# CAN_ProtoBoard_Pro_Mini.net
KiCad netlist of a schematic drawn in EAGLE
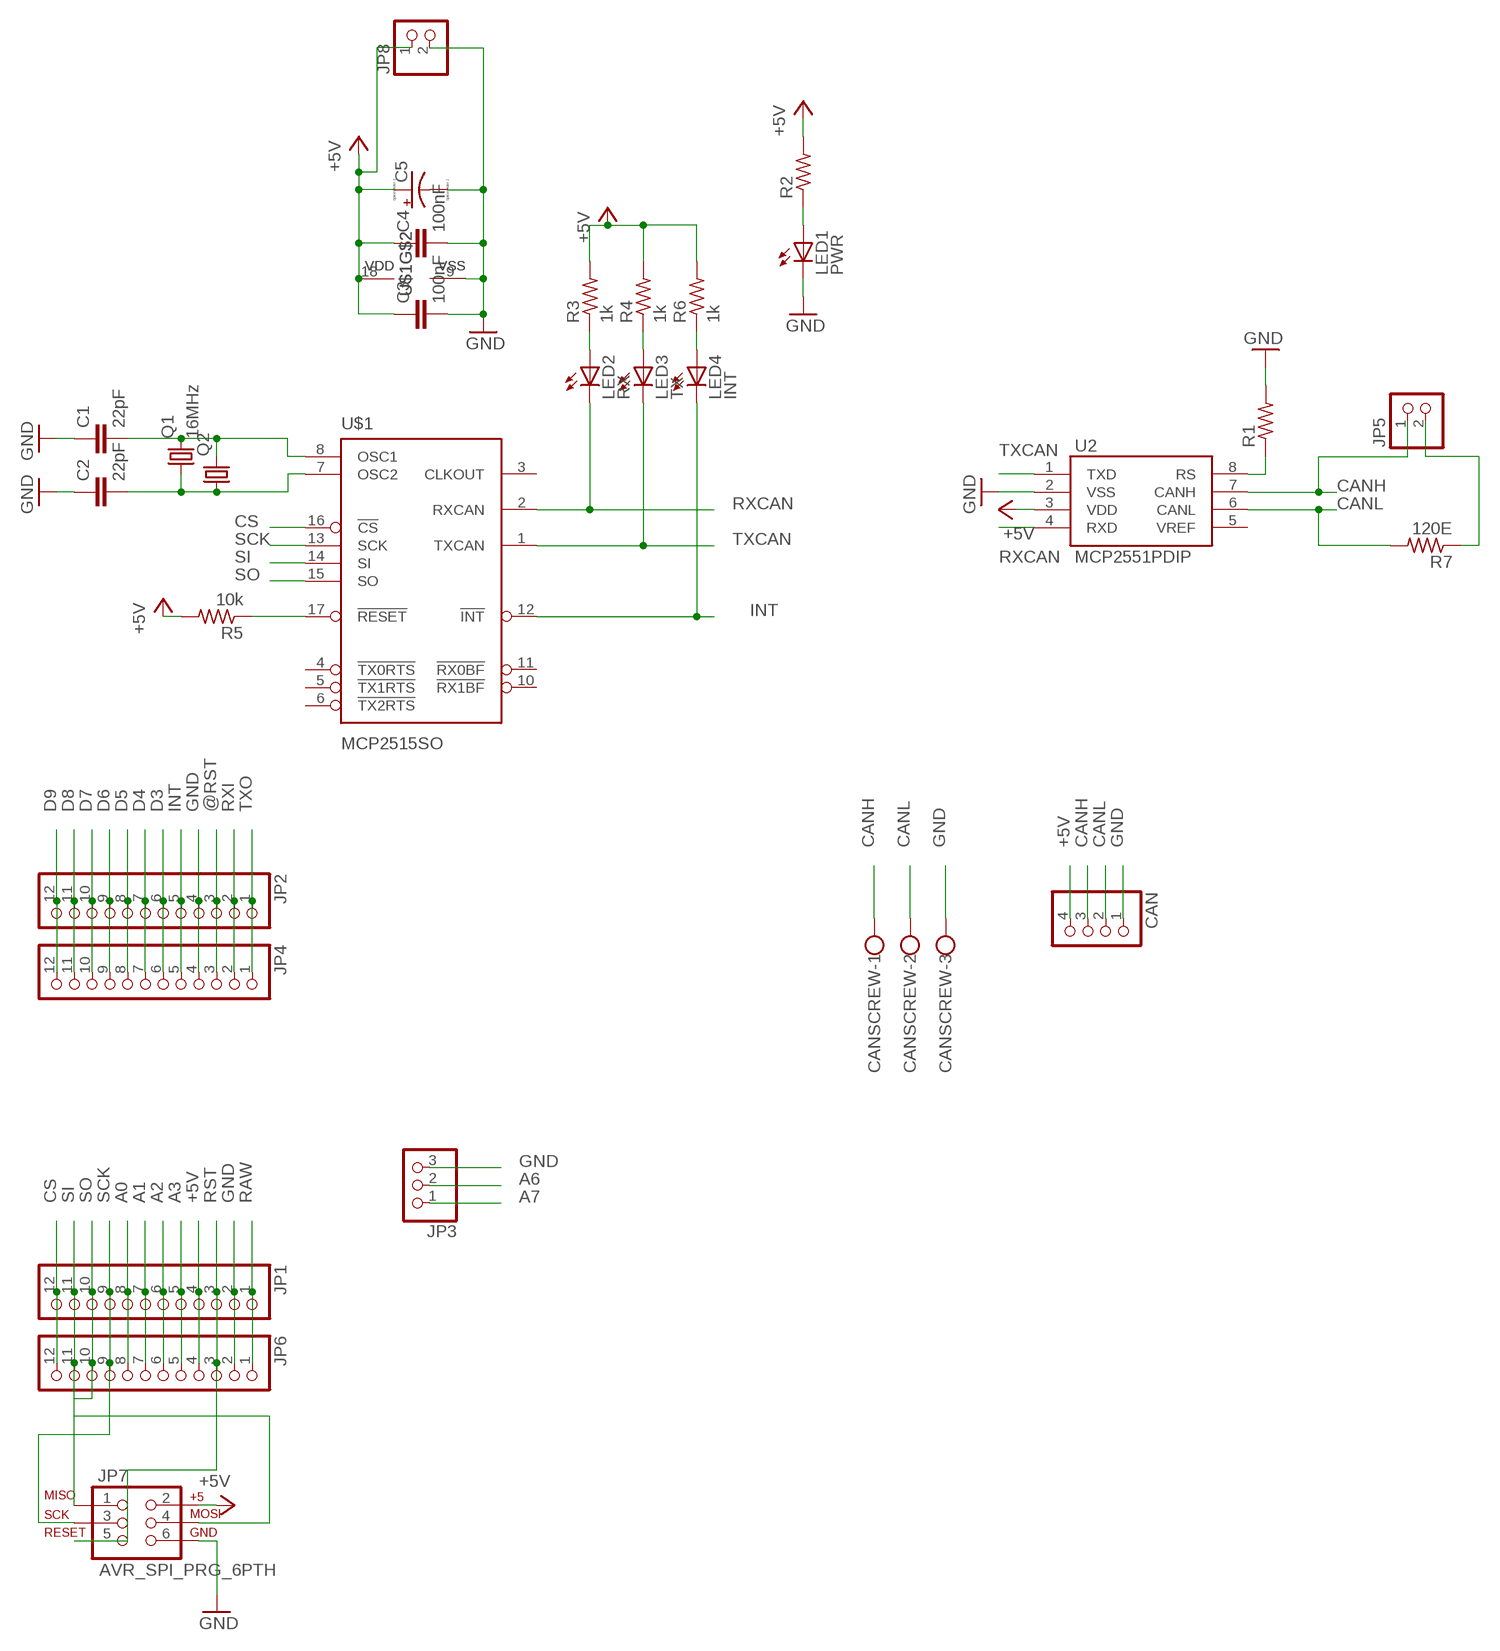
[diagram p0: schematic, sheet 1]

(export (version "E")
  (design (tool "Eeschema 10.0.6"))
  (components
    (comp (ref "C1")
      (value "22pF")
      (footprint "eagle-import:C0805K")
      (libsource (lib "eagle-import") (part "C-EUC0805K"))
    )
    (comp (ref "C2")
      (value "22pF")
      (footprint "eagle-import:C0805K")
      (libsource (lib "eagle-import") (part "C-EUC0805K"))
    )
    (comp (ref "C3")
      (value "100nF")
      (footprint "eagle-import:C0805K")
      (libsource (lib "eagle-import") (part "C-EUC0805K"))
    )
    (comp (ref "C4")
      (value "100nF")
      (footprint "eagle-import:C0805K")
      (libsource (lib "eagle-import") (part "C-EUC0805K"))
    )
    (comp (ref "C5")
      (value "CPOL-USE5-8.5")
      (footprint "eagle-import:E5-8,5")
      (libsource (lib "eagle-import") (part "CPOL-USE5-8.5"))
    )
    (comp (ref "CAN")
      (value "PINHD-1X4")
      (footprint "eagle-import:1X04")
      (libsource (lib "eagle-import") (part "PINHD-1X4"))
    )
    (comp (ref "CANSCREW")
      (value "W237-103")
      (footprint "eagle-import:W237-103")
      (fields (field (name "MPN") "237-103"))
      (libsource (lib "eagle-import") (part "W237-103"))
    )
    (comp (ref "JP1")
      (value "PINHD-1X12")
      (footprint "eagle-import:1X12")
      (libsource (lib "eagle-import") (part "PINHD-1X12"))
    )
    (comp (ref "JP2")
      (value "PINHD-1X12")
      (footprint "eagle-import:1X12")
      (libsource (lib "eagle-import") (part "PINHD-1X12"))
    )
    (comp (ref "JP3")
      (value "PINHD-1X3")
      (footprint "eagle-import:1X03")
      (libsource (lib "eagle-import") (part "PINHD-1X3"))
    )
    (comp (ref "JP4")
      (value "PINHD-1X12")
      (footprint "eagle-import:1X12")
      (libsource (lib "eagle-import") (part "PINHD-1X12"))
    )
    (comp (ref "JP5")
      (value "PINHD-1X2")
      (footprint "eagle-import:1X02")
      (libsource (lib "eagle-import") (part "PINHD-1X2"))
    )
    (comp (ref "JP6")
      (value "PINHD-1X12")
      (footprint "eagle-import:1X12")
      (libsource (lib "eagle-import") (part "PINHD-1X12"))
    )
    (comp (ref "JP7")
      (value "AVR_SPI_PRG_6PTH")
      (footprint "eagle-import:2X3")
      (libsource (lib "eagle-import") (part "AVR_SPI_PRG_6PTH"))
    )
    (comp (ref "JP8")
      (value "PINHD-1X2")
      (footprint "eagle-import:1X02")
      (libsource (lib "eagle-import") (part "PINHD-1X2"))
    )
    (comp (ref "LED1")
      (value "PWR")
      (footprint "eagle-import:LED3MM")
      (libsource (lib "eagle-import") (part "LED3MM"))
    )
    (comp (ref "LED2")
      (value "RX")
      (footprint "eagle-import:LED3MM")
      (libsource (lib "eagle-import") (part "LED3MM"))
    )
    (comp (ref "LED3")
      (value "TX")
      (footprint "eagle-import:LED3MM")
      (libsource (lib "eagle-import") (part "LED3MM"))
    )
    (comp (ref "LED4")
      (value "INT")
      (footprint "eagle-import:LED3MM")
      (libsource (lib "eagle-import") (part "LED3MM"))
    )
    (comp (ref "Q1")
      (value "16MHz")
      (footprint "eagle-import:HC49_S")
      (libsource (lib "eagle-import") (part "CRYSTALHC49S"))
    )
    (comp (ref "Q2")
      (value "CRYSTALHC49UP")
      (footprint "eagle-import:HC49UP")
      (libsource (lib "eagle-import") (part "CRYSTALHC49UP"))
    )
    (comp (ref "R1")
      (value "R-US_R0805")
      (footprint "eagle-import:R0805")
      (libsource (lib "eagle-import") (part "R-US_R0805"))
    )
    (comp (ref "R2")
      (value "R-US_R0805")
      (footprint "eagle-import:R0805")
      (libsource (lib "eagle-import") (part "R-US_R0805"))
    )
    (comp (ref "R3")
      (value "1k")
      (footprint "eagle-import:R0805")
      (libsource (lib "eagle-import") (part "R-US_R0805"))
    )
    (comp (ref "R4")
      (value "1k")
      (footprint "eagle-import:R0805")
      (libsource (lib "eagle-import") (part "R-US_R0805"))
    )
    (comp (ref "R5")
      (value "10k")
      (footprint "eagle-import:R0805")
      (libsource (lib "eagle-import") (part "R-US_R0805"))
    )
    (comp (ref "R6")
      (value "1k")
      (footprint "eagle-import:R0805")
      (libsource (lib "eagle-import") (part "R-US_R0805"))
    )
    (comp (ref "R7")
      (value "120E")
      (footprint "eagle-import:R0805")
      (libsource (lib "eagle-import") (part "R-US_R0805"))
    )
    (comp (ref "U$1")
      (value "MCP2515SO")
      (footprint "eagle-import:SO-18W")
      (libsource (lib "eagle-import") (part "MCP2515SO"))
    )
    (comp (ref "U2")
      (value "MCP2551PDIP")
      (footprint "eagle-import:DIL08")
      (libsource (lib "eagle-import") (part "MCP2551PDIP"))
    )
  )
  (nets
    (net (code "1") (name "+5V") (class "Default")
      (node (ref "C3") (pin "1") (pinfunction "1_1") (pintype "passive"))
      (node (ref "C4") (pin "1") (pinfunction "1_1") (pintype "passive"))
      (node (ref "C5") (pin "+") (pinfunction "+_+") (pintype "passive"))
      (node (ref "CAN") (pin "4") (pinfunction "4_4") (pintype "passive"))
      (node (ref "JP1") (pin "4") (pinfunction "4_4") (pintype "passive"))
      (node (ref "JP6") (pin "4") (pinfunction "4_4") (pintype "passive"))
      (node (ref "JP7") (pin "2") (pinfunction "2_2") (pintype "passive"))
      (node (ref "JP8") (pin "1") (pinfunction "1_1") (pintype "passive"))
      (node (ref "R2") (pin "2") (pinfunction "2_2") (pintype "passive"))
      (node (ref "R3") (pin "2") (pinfunction "2_2") (pintype "passive"))
      (node (ref "R4") (pin "2") (pinfunction "2_2") (pintype "passive"))
      (node (ref "R5") (pin "2") (pinfunction "2_2") (pintype "passive"))
      (node (ref "R6") (pin "2") (pinfunction "2_2") (pintype "passive"))
      (node (ref "U$1") (pin "18") (pinfunction "VDD_18") (pintype "power_in"))
      (node (ref "U2") (pin "3") (pinfunction "VDD_3") (pintype "bidirectional"))
    )
    (net (code "2") (name "/@RST") (class "Default")
      (node (ref "JP2") (pin "3") (pinfunction "3_3") (pintype "passive"))
      (node (ref "JP4") (pin "3") (pinfunction "3_3") (pintype "passive"))
    )
    (net (code "3") (name "/A0") (class "Default")
      (node (ref "JP1") (pin "8") (pinfunction "8_8") (pintype "passive"))
      (node (ref "JP6") (pin "8") (pinfunction "8_8") (pintype "passive"))
    )
    (net (code "4") (name "/A1") (class "Default")
      (node (ref "JP1") (pin "7") (pinfunction "7_7") (pintype "passive"))
      (node (ref "JP6") (pin "7") (pinfunction "7_7") (pintype "passive"))
    )
    (net (code "5") (name "/A2") (class "Default")
      (node (ref "JP1") (pin "6") (pinfunction "6_6") (pintype "passive"))
      (node (ref "JP6") (pin "6") (pinfunction "6_6") (pintype "passive"))
    )
    (net (code "6") (name "/A3") (class "Default")
      (node (ref "JP1") (pin "5") (pinfunction "5_5") (pintype "passive"))
      (node (ref "JP6") (pin "5") (pinfunction "5_5") (pintype "passive"))
    )
    (net (code "7") (name "/A6") (class "Default")
      (node (ref "JP3") (pin "2") (pinfunction "2_2") (pintype "passive"))
    )
    (net (code "8") (name "/A7") (class "Default")
      (node (ref "JP3") (pin "1") (pinfunction "1_1") (pintype "passive"))
    )
    (net (code "9") (name "/CANH") (class "Default")
      (node (ref "CAN") (pin "3") (pinfunction "3_3") (pintype "passive"))
      (node (ref "CANSCREW") (pin "1") (pinfunction "KL_1") (pintype "passive"))
      (node (ref "JP5") (pin "1") (pinfunction "1_1") (pintype "passive"))
      (node (ref "U2") (pin "7") (pinfunction "CANH_7") (pintype "bidirectional"))
    )
    (net (code "10") (name "/CANL") (class "Default")
      (node (ref "CAN") (pin "2") (pinfunction "2_2") (pintype "passive"))
      (node (ref "CANSCREW") (pin "2") (pinfunction "KL_2") (pintype "passive"))
      (node (ref "R7") (pin "2") (pinfunction "2_2") (pintype "passive"))
      (node (ref "U2") (pin "6") (pinfunction "CANL_6") (pintype "bidirectional"))
    )
    (net (code "11") (name "/CS") (class "Default")
      (node (ref "JP1") (pin "12") (pinfunction "12_12") (pintype "passive"))
      (node (ref "JP6") (pin "12") (pinfunction "12_12") (pintype "passive"))
      (node (ref "U$1") (pin "16") (pinfunction "~{CS}_16") (pintype "input"))
    )
    (net (code "12") (name "/D3") (class "Default")
      (node (ref "JP2") (pin "6") (pinfunction "6_6") (pintype "passive"))
      (node (ref "JP4") (pin "6") (pinfunction "6_6") (pintype "passive"))
    )
    (net (code "13") (name "/D4") (class "Default")
      (node (ref "JP2") (pin "7") (pinfunction "7_7") (pintype "passive"))
      (node (ref "JP4") (pin "7") (pinfunction "7_7") (pintype "passive"))
    )
    (net (code "14") (name "/D5") (class "Default")
      (node (ref "JP2") (pin "8") (pinfunction "8_8") (pintype "passive"))
      (node (ref "JP4") (pin "8") (pinfunction "8_8") (pintype "passive"))
    )
    (net (code "15") (name "/D6") (class "Default")
      (node (ref "JP2") (pin "9") (pinfunction "9_9") (pintype "passive"))
      (node (ref "JP4") (pin "9") (pinfunction "9_9") (pintype "passive"))
    )
    (net (code "16") (name "/D7") (class "Default")
      (node (ref "JP2") (pin "10") (pinfunction "10_10") (pintype "passive"))
      (node (ref "JP4") (pin "10") (pinfunction "10_10") (pintype "passive"))
    )
    (net (code "17") (name "/D8") (class "Default")
      (node (ref "JP2") (pin "11") (pinfunction "11_11") (pintype "passive"))
      (node (ref "JP4") (pin "11") (pinfunction "11_11") (pintype "passive"))
    )
    (net (code "18") (name "/D9") (class "Default")
      (node (ref "JP2") (pin "12") (pinfunction "12_12") (pintype "passive"))
      (node (ref "JP4") (pin "12") (pinfunction "12_12") (pintype "passive"))
    )
    (net (code "19") (name "/INT") (class "Default")
      (node (ref "JP2") (pin "5") (pinfunction "5_5") (pintype "passive"))
      (node (ref "JP4") (pin "5") (pinfunction "5_5") (pintype "passive"))
      (node (ref "LED4") (pin "K") (pinfunction "C_K") (pintype "passive"))
      (node (ref "U$1") (pin "12") (pinfunction "~{INT}_12") (pintype "output"))
    )
    (net (code "20") (name "/RAW") (class "Default")
      (node (ref "JP1") (pin "1") (pinfunction "1_1") (pintype "passive"))
      (node (ref "JP6") (pin "1") (pinfunction "1_1") (pintype "passive"))
    )
    (net (code "21") (name "/RST") (class "Default")
      (node (ref "JP1") (pin "3") (pinfunction "3_3") (pintype "passive"))
      (node (ref "JP6") (pin "3") (pinfunction "3_3") (pintype "passive"))
      (node (ref "JP7") (pin "5") (pinfunction "5_5") (pintype "passive"))
    )
    (net (code "22") (name "/RXCAN") (class "Default")
      (node (ref "LED2") (pin "K") (pinfunction "C_K") (pintype "passive"))
      (node (ref "U$1") (pin "2") (pinfunction "RXCAN_2") (pintype "input"))
      (node (ref "U2") (pin "4") (pinfunction "RXD_4") (pintype "bidirectional"))
    )
    (net (code "23") (name "/RXI") (class "Default")
      (node (ref "JP2") (pin "2") (pinfunction "2_2") (pintype "passive"))
      (node (ref "JP4") (pin "2") (pinfunction "2_2") (pintype "passive"))
    )
    (net (code "24") (name "/SCK") (class "Default")
      (node (ref "JP1") (pin "9") (pinfunction "9_9") (pintype "passive"))
      (node (ref "JP6") (pin "9") (pinfunction "9_9") (pintype "passive"))
      (node (ref "JP7") (pin "3") (pinfunction "3_3") (pintype "passive"))
      (node (ref "U$1") (pin "13") (pinfunction "SCK_13") (pintype "input"))
    )
    (net (code "25") (name "/SI") (class "Default")
      (node (ref "JP1") (pin "11") (pinfunction "11_11") (pintype "passive"))
      (node (ref "JP6") (pin "11") (pinfunction "11_11") (pintype "passive"))
      (node (ref "JP7") (pin "4") (pinfunction "4_4") (pintype "passive"))
      (node (ref "U$1") (pin "14") (pinfunction "SI_14") (pintype "input"))
    )
    (net (code "26") (name "/SO") (class "Default")
      (node (ref "JP1") (pin "10") (pinfunction "10_10") (pintype "passive"))
      (node (ref "JP6") (pin "10") (pinfunction "10_10") (pintype "passive"))
      (node (ref "JP7") (pin "1") (pinfunction "1_1") (pintype "passive"))
      (node (ref "U$1") (pin "15") (pinfunction "SO_15") (pintype "output"))
    )
    (net (code "27") (name "/TXCAN") (class "Default")
      (node (ref "LED3") (pin "K") (pinfunction "C_K") (pintype "passive"))
      (node (ref "U$1") (pin "1") (pinfunction "TXCAN_1") (pintype "output"))
      (node (ref "U2") (pin "1") (pinfunction "TXD_1") (pintype "bidirectional"))
    )
    (net (code "28") (name "/TXO") (class "Default")
      (node (ref "JP2") (pin "1") (pinfunction "1_1") (pintype "passive"))
      (node (ref "JP4") (pin "1") (pinfunction "1_1") (pintype "passive"))
    )
    (net (code "29") (name "GND") (class "Default")
      (node (ref "C1") (pin "1") (pinfunction "1_1") (pintype "passive"))
      (node (ref "C2") (pin "1") (pinfunction "1_1") (pintype "passive"))
      (node (ref "C3") (pin "2") (pinfunction "2_2") (pintype "passive"))
      (node (ref "C4") (pin "2") (pinfunction "2_2") (pintype "passive"))
      (node (ref "C5") (pin "-") (pinfunction "-_-") (pintype "passive"))
      (node (ref "CAN") (pin "1") (pinfunction "1_1") (pintype "passive"))
      (node (ref "CANSCREW") (pin "3") (pinfunction "KL_3") (pintype "passive"))
      (node (ref "JP1") (pin "2") (pinfunction "2_2") (pintype "passive"))
      (node (ref "JP2") (pin "4") (pinfunction "4_4") (pintype "passive"))
      (node (ref "JP3") (pin "3") (pinfunction "3_3") (pintype "passive"))
      (node (ref "JP4") (pin "4") (pinfunction "4_4") (pintype "passive"))
      (node (ref "JP6") (pin "2") (pinfunction "2_2") (pintype "passive"))
      (node (ref "JP7") (pin "6") (pinfunction "6_6") (pintype "passive"))
      (node (ref "JP8") (pin "2") (pinfunction "2_2") (pintype "passive"))
      (node (ref "LED1") (pin "K") (pinfunction "C_K") (pintype "passive"))
      (node (ref "R1") (pin "2") (pinfunction "2_2") (pintype "passive"))
      (node (ref "U$1") (pin "9") (pinfunction "VSS_9") (pintype "power_in"))
      (node (ref "U2") (pin "2") (pinfunction "VSS_2") (pintype "bidirectional"))
    )
    (net (code "30") (name "Net-(JP5-Pad2)") (class "Default")
      (node (ref "JP5") (pin "2") (pinfunction "2_2") (pintype "passive"))
      (node (ref "R7") (pin "1") (pinfunction "1_1") (pintype "passive"))
    )
    (net (code "31") (name "Net-(LED1-PadA)") (class "Default")
      (node (ref "LED1") (pin "A") (pinfunction "A_A") (pintype "passive"))
      (node (ref "R2") (pin "1") (pinfunction "1_1") (pintype "passive"))
    )
    (net (code "32") (name "Net-(LED2-PadA)") (class "Default")
      (node (ref "LED2") (pin "A") (pinfunction "A_A") (pintype "passive"))
      (node (ref "R3") (pin "1") (pinfunction "1_1") (pintype "passive"))
    )
    (net (code "33") (name "Net-(LED3-PadA)") (class "Default")
      (node (ref "LED3") (pin "A") (pinfunction "A_A") (pintype "passive"))
      (node (ref "R4") (pin "1") (pinfunction "1_1") (pintype "passive"))
    )
    (net (code "34") (name "Net-(LED4-PadA)") (class "Default")
      (node (ref "LED4") (pin "A") (pinfunction "A_A") (pintype "passive"))
      (node (ref "R6") (pin "1") (pinfunction "1_1") (pintype "passive"))
    )
    (net (code "35") (name "Net-(U$1A-OSC1)") (class "Default")
      (node (ref "C1") (pin "2") (pinfunction "2_2") (pintype "passive"))
      (node (ref "Q1") (pin "2") (pinfunction "2_2") (pintype "passive"))
      (node (ref "Q2") (pin "2") (pinfunction "2_2") (pintype "passive"))
      (node (ref "U$1") (pin "8") (pinfunction "OSC1_8") (pintype "input"))
    )
    (net (code "36") (name "Net-(U$1A-OSC2)") (class "Default")
      (node (ref "C2") (pin "2") (pinfunction "2_2") (pintype "passive"))
      (node (ref "Q1") (pin "1") (pinfunction "1_1") (pintype "passive"))
      (node (ref "Q2") (pin "1") (pinfunction "1_1") (pintype "passive"))
      (node (ref "U$1") (pin "7") (pinfunction "OSC2_7") (pintype "output"))
    )
    (net (code "37") (name "Net-(U$1A-~{RESET})") (class "Default")
      (node (ref "R5") (pin "1") (pinfunction "1_1") (pintype "passive"))
      (node (ref "U$1") (pin "17") (pinfunction "~{RESET}_17") (pintype "input"))
    )
    (net (code "38") (name "Net-(U2-RS)") (class "Default")
      (node (ref "R1") (pin "1") (pinfunction "1_1") (pintype "passive"))
      (node (ref "U2") (pin "8") (pinfunction "RS_8") (pintype "bidirectional"))
    )
    (net (code "39") (name "unconnected-(U$1A-CLKOUT-Pad3)") (class "Default")
      (node (ref "U$1") (pin "3") (pinfunction "CLKOUT_3") (pintype "output"))
    )
    (net (code "40") (name "unconnected-(U$1A-~{RX0BF}-Pad11)") (class "Default")
      (node (ref "U$1") (pin "11") (pinfunction "~{RX0BF}_11") (pintype "output"))
    )
    (net (code "41") (name "unconnected-(U$1A-~{RX1BF}-Pad10)") (class "Default")
      (node (ref "U$1") (pin "10") (pinfunction "~{RX1BF}_10") (pintype "output"))
    )
    (net (code "42") (name "unconnected-(U$1A-~{TX0RTS}-Pad4)") (class "Default")
      (node (ref "U$1") (pin "4") (pinfunction "~{TX0RTS}_4") (pintype "input"))
    )
    (net (code "43") (name "unconnected-(U$1A-~{TX1RTS}-Pad5)") (class "Default")
      (node (ref "U$1") (pin "5") (pinfunction "~{TX1RTS}_5") (pintype "input"))
    )
    (net (code "44") (name "unconnected-(U$1A-~{TX2RTS}-Pad6)") (class "Default")
      (node (ref "U$1") (pin "6") (pinfunction "~{TX2RTS}_6") (pintype "input"))
    )
    (net (code "45") (name "unconnected-(U2-VREF-Pad5)") (class "Default")
      (node (ref "U2") (pin "5") (pinfunction "VREF_5") (pintype "bidirectional"))
    )
  )
)
